# Espectrometro_Peri.net
KiCad netlist of a schematic drawn in Altium Designer
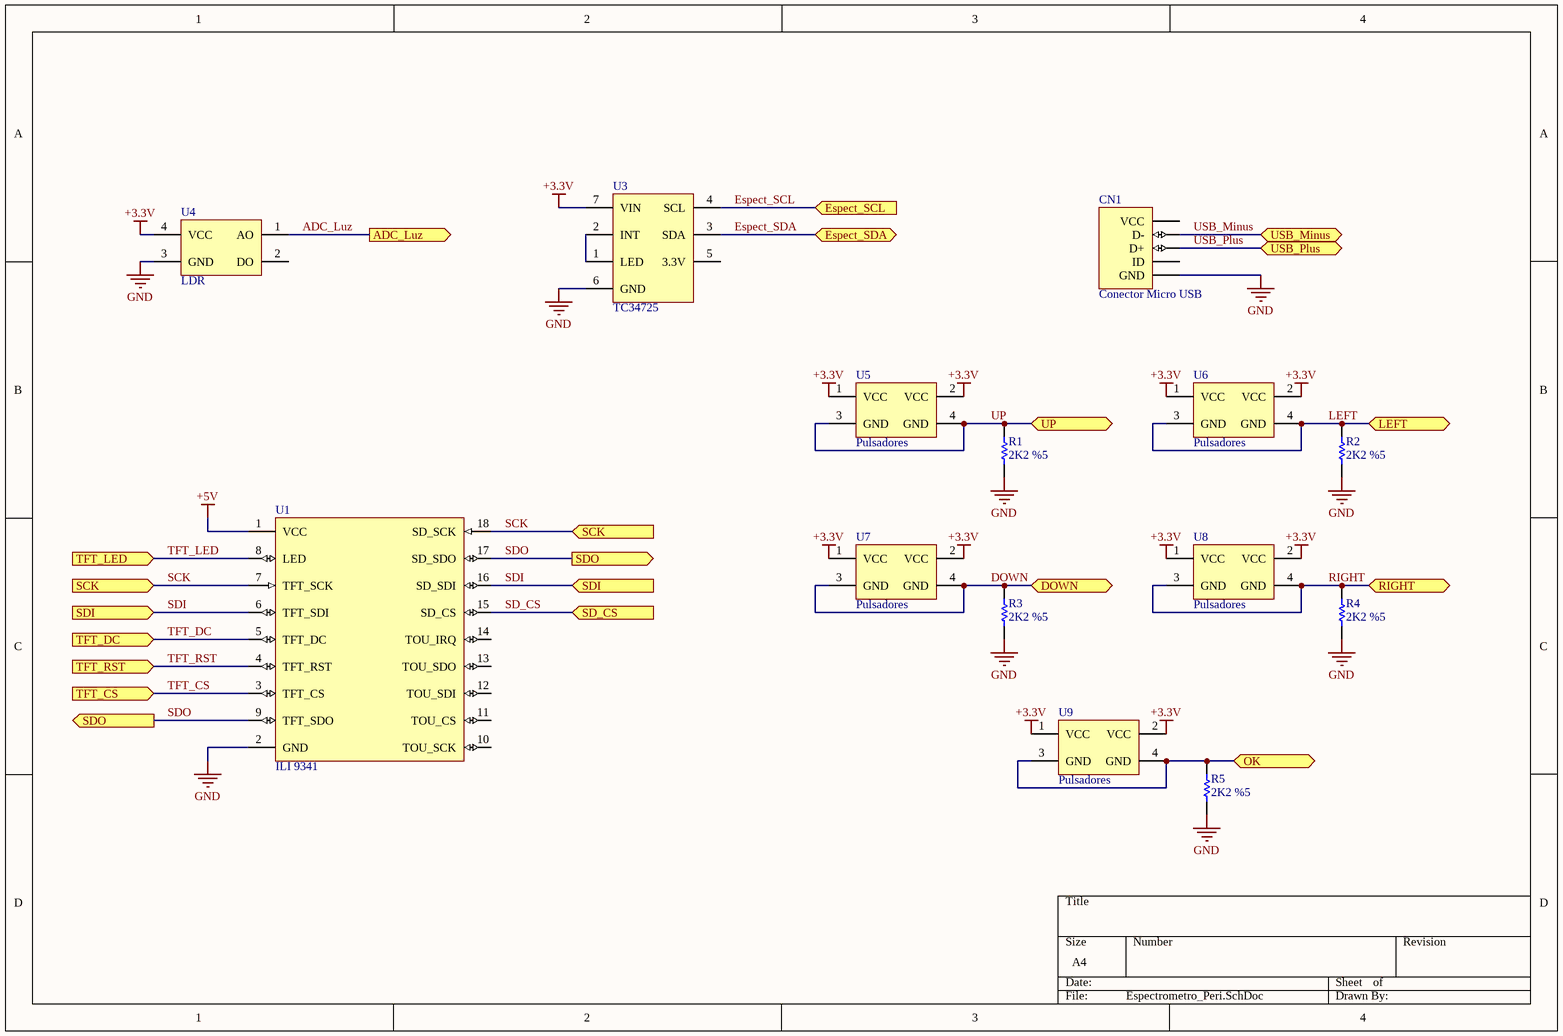
[diagram p0: Espectrometro_Peri.SchDoc]

(export (version "E")
  (design (tool "Eeschema 10.0.6"))
  (components
    (comp (ref "CN1")
      (value "Conector Micro USB")
      (footprint "C8320-05BFRIB0R")
      (description "Conector Micro USB Type B")
      (libsource (lib "Nucleo") (part "Conector Micro USB"))
    )
    (comp (ref "R1")
      (value "2K2 %5")
      (footprint "R_400")
      (description "Resistor")
      (fields (field (name "AUTHOR") "Franco Mendez"))
      (libsource (lib "Nucleo") (part "Resistencia"))
    )
    (comp (ref "R2")
      (value "2K2 %5")
      (footprint "R_400")
      (description "Resistor")
      (fields (field (name "AUTHOR") "Franco Mendez"))
      (libsource (lib "Nucleo") (part "Resistencia"))
    )
    (comp (ref "R3")
      (value "2K2 %5")
      (footprint "R_400")
      (description "Resistor")
      (fields (field (name "AUTHOR") "Franco Mendez"))
      (libsource (lib "Nucleo") (part "Resistencia"))
    )
    (comp (ref "R4")
      (value "2K2 %5")
      (footprint "R_400")
      (description "Resistor")
      (fields (field (name "AUTHOR") "Franco Mendez"))
      (libsource (lib "Nucleo") (part "Resistencia"))
    )
    (comp (ref "R5")
      (value "2K2 %5")
      (footprint "R_400")
      (description "Resistor")
      (fields (field (name "AUTHOR") "Franco Mendez"))
      (libsource (lib "Nucleo") (part "Resistencia"))
    )
    (comp (ref "U1")
      (value "ILI 9341")
      (footprint "Pantalla_TFT_2.4\"")
      (description "Pantalla TFT 2.4\"")
      (libsource (lib "Nucleo") (part "PantallaTFT"))
    )
    (comp (ref "U3")
      (value "TC34725")
      (footprint "TC34725")
      (description "Sensor RGB")
      (libsource (lib "Nucleo") (part "TC34725"))
    )
    (comp (ref "U4")
      (value "LDR")
      (footprint "HEADER_M-4x1_0.1\"_H")
      (description "Sensor LDR para medir Int.Luz")
      (libsource (lib "Nucleo") (part "LDR"))
    )
    (comp (ref "U5")
      (value "Pulsadores")
      (footprint "Tact Switch TH")
      (description "Tact Switch")
      (libsource (lib "Nucleo") (part "Pulsadores"))
    )
    (comp (ref "U6")
      (value "Pulsadores")
      (footprint "Tact Switch TH")
      (description "Tact Switch")
      (libsource (lib "Nucleo") (part "Pulsadores"))
    )
    (comp (ref "U7")
      (value "Pulsadores")
      (footprint "Tact Switch TH")
      (description "Tact Switch")
      (libsource (lib "Nucleo") (part "Pulsadores"))
    )
    (comp (ref "U8")
      (value "Pulsadores")
      (footprint "Tact Switch TH")
      (description "Tact Switch")
      (libsource (lib "Nucleo") (part "Pulsadores"))
    )
    (comp (ref "U9")
      (value "Pulsadores")
      (footprint "Tact Switch TH")
      (description "Tact Switch")
      (libsource (lib "Nucleo") (part "Pulsadores"))
    )
  )
  (nets
    (net (code "1") (name "+3.3V") (class "Default")
      (node (ref "U3") (pin "7") (pinfunction "VIN_7") (pintype "passive"))
      (node (ref "U4") (pin "4") (pinfunction "VCC_4") (pintype "power_in"))
      (node (ref "U5") (pin "1") (pinfunction "VCC_1") (pintype "passive"))
      (node (ref "U5") (pin "2") (pinfunction "VCC_2") (pintype "passive"))
      (node (ref "U6") (pin "1") (pinfunction "VCC_1") (pintype "passive"))
      (node (ref "U6") (pin "2") (pinfunction "VCC_2") (pintype "passive"))
      (node (ref "U7") (pin "1") (pinfunction "VCC_1") (pintype "passive"))
      (node (ref "U7") (pin "2") (pinfunction "VCC_2") (pintype "passive"))
      (node (ref "U8") (pin "1") (pinfunction "VCC_1") (pintype "passive"))
      (node (ref "U8") (pin "2") (pinfunction "VCC_2") (pintype "passive"))
      (node (ref "U9") (pin "1") (pinfunction "VCC_1") (pintype "passive"))
      (node (ref "U9") (pin "2") (pinfunction "VCC_2") (pintype "passive"))
    )
    (net (code "2") (name "+5V") (class "Default")
      (node (ref "U1") (pin "1") (pinfunction "VCC_1") (pintype "power_in"))
    )
    (net (code "3") (name "/ADC_Luz") (class "Default")
      (node (ref "U4") (pin "1") (pinfunction "AO_1") (pintype "passive"))
    )
    (net (code "4") (name "/DOWN") (class "Default")
      (node (ref "R3") (pin "1") (pinfunction "1_1") (pintype "passive"))
      (node (ref "U7") (pin "3") (pinfunction "GND_3") (pintype "passive"))
      (node (ref "U7") (pin "4") (pinfunction "GND_4") (pintype "passive"))
    )
    (net (code "5") (name "/Espect_SCL") (class "Default")
      (node (ref "U3") (pin "4") (pinfunction "SCL_4") (pintype "passive"))
    )
    (net (code "6") (name "/Espect_SDA") (class "Default")
      (node (ref "U3") (pin "3") (pinfunction "SDA_3") (pintype "passive"))
    )
    (net (code "7") (name "/LEFT") (class "Default")
      (node (ref "R2") (pin "1") (pinfunction "1_1") (pintype "passive"))
      (node (ref "U6") (pin "3") (pinfunction "GND_3") (pintype "passive"))
      (node (ref "U6") (pin "4") (pinfunction "GND_4") (pintype "passive"))
    )
    (net (code "8") (name "/OK") (class "Default")
      (node (ref "R5") (pin "1") (pinfunction "1_1") (pintype "passive"))
      (node (ref "U9") (pin "3") (pinfunction "GND_3") (pintype "passive"))
      (node (ref "U9") (pin "4") (pinfunction "GND_4") (pintype "passive"))
    )
    (net (code "9") (name "/RIGHT") (class "Default")
      (node (ref "R4") (pin "1") (pinfunction "1_1") (pintype "passive"))
      (node (ref "U8") (pin "3") (pinfunction "GND_3") (pintype "passive"))
      (node (ref "U8") (pin "4") (pinfunction "GND_4") (pintype "passive"))
    )
    (net (code "10") (name "/SCK") (class "Default")
      (node (ref "U1") (pin "18") (pinfunction "SD_SCK_18") (pintype "input"))
      (node (ref "U1") (pin "7") (pinfunction "TFT_SCK_7") (pintype "input"))
    )
    (net (code "11") (name "/SDI") (class "Default")
      (node (ref "U1") (pin "16") (pinfunction "SD_SDI_16") (pintype "bidirectional"))
      (node (ref "U1") (pin "6") (pinfunction "TFT_SDI_6") (pintype "bidirectional"))
    )
    (net (code "12") (name "/SDO") (class "Default")
      (node (ref "U1") (pin "17") (pinfunction "SD_SDO_17") (pintype "bidirectional"))
      (node (ref "U1") (pin "9") (pinfunction "TFT_SDO_9") (pintype "bidirectional"))
    )
    (net (code "13") (name "/SD_CS") (class "Default")
      (node (ref "U1") (pin "15") (pinfunction "SD_CS_15") (pintype "bidirectional"))
    )
    (net (code "14") (name "/TFT_CS") (class "Default")
      (node (ref "U1") (pin "3") (pinfunction "TFT_CS_3") (pintype "bidirectional"))
    )
    (net (code "15") (name "/TFT_DC") (class "Default")
      (node (ref "U1") (pin "5") (pinfunction "TFT_DC_5") (pintype "bidirectional"))
    )
    (net (code "16") (name "/TFT_LED") (class "Default")
      (node (ref "U1") (pin "8") (pinfunction "LED_8") (pintype "bidirectional"))
    )
    (net (code "17") (name "/TFT_RST") (class "Default")
      (node (ref "U1") (pin "4") (pinfunction "TFT_RST_4") (pintype "bidirectional"))
    )
    (net (code "18") (name "/UP") (class "Default")
      (node (ref "R1") (pin "1") (pinfunction "1_1") (pintype "passive"))
      (node (ref "U5") (pin "3") (pinfunction "GND_3") (pintype "passive"))
      (node (ref "U5") (pin "4") (pinfunction "GND_4") (pintype "passive"))
    )
    (net (code "19") (name "/USB_Minus") (class "Default")
      (node (ref "CN1") (pin "2") (pinfunction "D-_2") (pintype "bidirectional"))
    )
    (net (code "20") (name "/USB_Plus") (class "Default")
      (node (ref "CN1") (pin "3") (pinfunction "D+_3") (pintype "bidirectional"))
    )
    (net (code "21") (name "GND") (class "Default")
      (node (ref "CN1") (pin "5") (pinfunction "GND_5") (pintype "passive"))
      (node (ref "R1") (pin "2") (pinfunction "2_2") (pintype "passive"))
      (node (ref "R2") (pin "2") (pinfunction "2_2") (pintype "passive"))
      (node (ref "R3") (pin "2") (pinfunction "2_2") (pintype "passive"))
      (node (ref "R4") (pin "2") (pinfunction "2_2") (pintype "passive"))
      (node (ref "R5") (pin "2") (pinfunction "2_2") (pintype "passive"))
      (node (ref "U1") (pin "2") (pinfunction "GND_2") (pintype "power_in"))
      (node (ref "U3") (pin "6") (pinfunction "GND_6") (pintype "passive"))
      (node (ref "U4") (pin "3") (pinfunction "GND_3") (pintype "power_in"))
    )
    (net (code "22") (name "Net-(U3-INT)") (class "Default")
      (node (ref "U3") (pin "1") (pinfunction "LED_1") (pintype "passive"))
      (node (ref "U3") (pin "2") (pinfunction "INT_2") (pintype "passive"))
    )
    (net (code "23") (name "unconnected-(CN1-ID-Pad4)") (class "Default")
      (node (ref "CN1") (pin "4") (pinfunction "ID_4") (pintype "power_in"))
    )
    (net (code "24") (name "unconnected-(CN1-VCC-Pad1)") (class "Default")
      (node (ref "CN1") (pin "1") (pinfunction "VCC_1") (pintype "power_in"))
    )
    (net (code "25") (name "unconnected-(U1-TOU_CS-Pad11)") (class "Default")
      (node (ref "U1") (pin "11") (pinfunction "TOU_CS_11") (pintype "bidirectional"))
    )
    (net (code "26") (name "unconnected-(U1-TOU_IRQ-Pad14)") (class "Default")
      (node (ref "U1") (pin "14") (pinfunction "TOU_IRQ_14") (pintype "bidirectional"))
    )
    (net (code "27") (name "unconnected-(U1-TOU_SCK-Pad10)") (class "Default")
      (node (ref "U1") (pin "10") (pinfunction "TOU_SCK_10") (pintype "bidirectional"))
    )
    (net (code "28") (name "unconnected-(U1-TOU_SDI-Pad12)") (class "Default")
      (node (ref "U1") (pin "12") (pinfunction "TOU_SDI_12") (pintype "bidirectional"))
    )
    (net (code "29") (name "unconnected-(U1-TOU_SDO-Pad13)") (class "Default")
      (node (ref "U1") (pin "13") (pinfunction "TOU_SDO_13") (pintype "bidirectional"))
    )
    (net (code "30") (name "unconnected-(U3-3.3V-Pad5)") (class "Default")
      (node (ref "U3") (pin "5") (pinfunction "3.3V_5") (pintype "passive"))
    )
    (net (code "31") (name "unconnected-(U4-DO-Pad2)") (class "Default")
      (node (ref "U4") (pin "2") (pinfunction "DO_2") (pintype "passive"))
    )
  )
)
